# 50hz_sensor.net
KiCad netlist of a schematic drawn in EAGLE
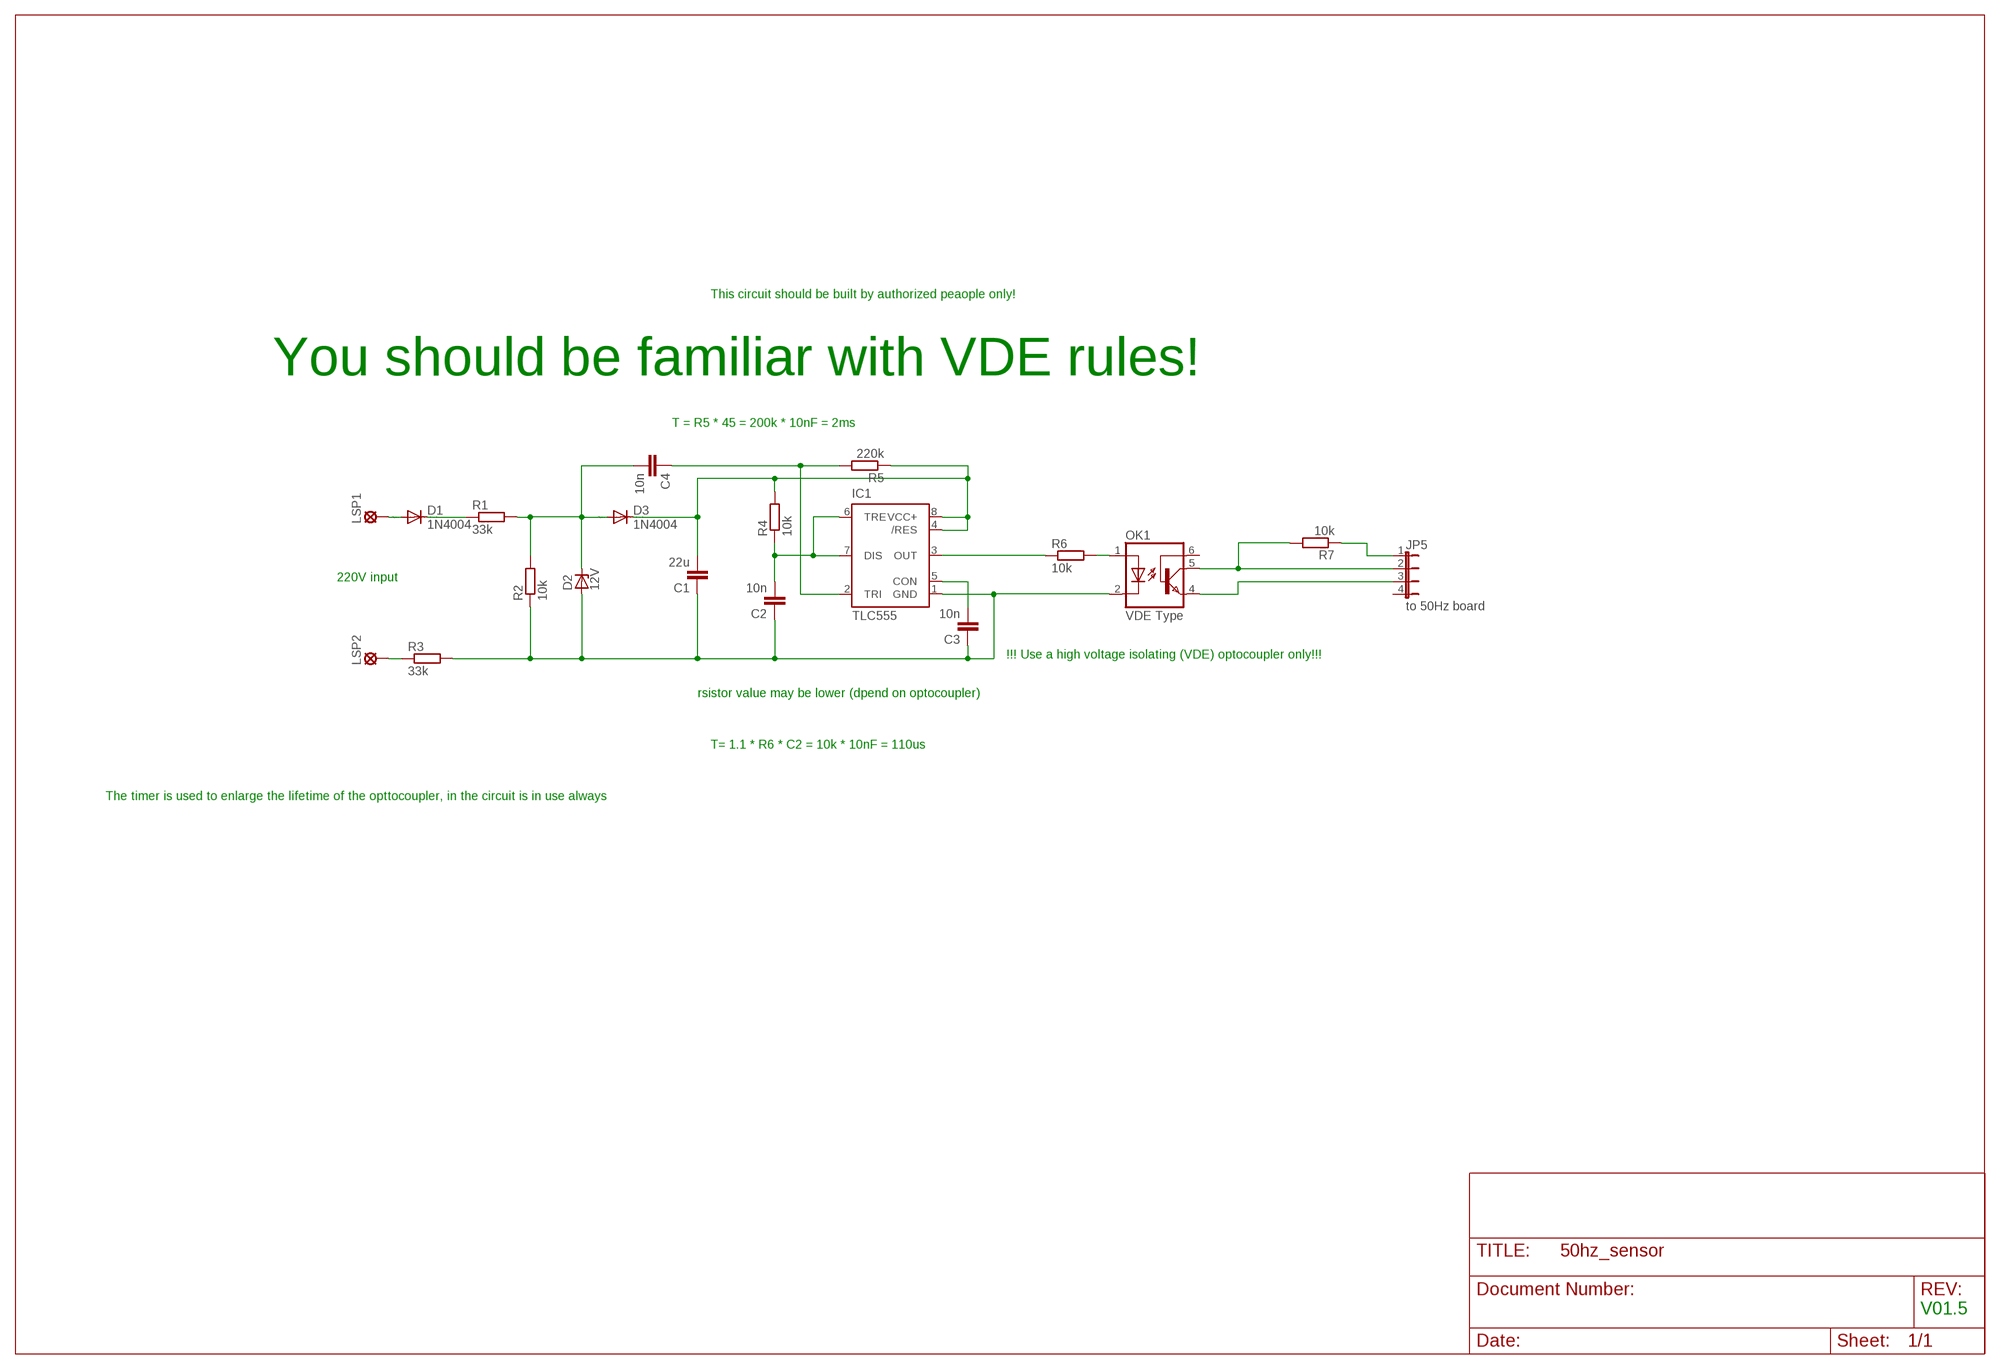
[diagram p0: schematic, sheet 1]

(export (version "E")
  (design (tool "Eeschema 10.0.6"))
  (components
    (comp (ref "C1")
      (value "22u")
      (footprint "eagle-import:C025-040X050")
      (libsource (lib "eagle-import") (part "C-EU025-040X050"))
    )
    (comp (ref "C2")
      (value "10n")
      (footprint "eagle-import:C050-025X075")
      (libsource (lib "eagle-import") (part "C-EU050-025X075"))
    )
    (comp (ref "C3")
      (value "10n")
      (footprint "eagle-import:C050-035X075")
      (libsource (lib "eagle-import") (part "C-EU050-035X075"))
    )
    (comp (ref "C4")
      (value "10n")
      (footprint "eagle-import:C050-030X075")
      (libsource (lib "eagle-import") (part "C-EU050-030X075"))
    )
    (comp (ref "D1")
      (value "1N4004")
      (footprint "eagle-import:DO41-10")
      (libsource (lib "eagle-import") (part "1N4004"))
    )
    (comp (ref "D2")
      (value "12V")
      (footprint "eagle-import:DO34Z7")
      (libsource (lib "eagle-import") (part "ZENER-DIODEDO34-7"))
    )
    (comp (ref "D3")
      (value "1N4004")
      (footprint "eagle-import:DO41-10")
      (libsource (lib "eagle-import") (part "1N4004"))
    )
    (comp (ref "IC1")
      (value "TLC555")
      (footprint "eagle-import:DIL-08")
      (fields (field (name "MF") "Arrow Electronics") (field (name "MPN") "NE555N"))
      (libsource (lib "eagle-import") (part "NE555"))
    )
    (comp (ref "JP5")
      (value "to 50Hz board")
      (footprint "eagle-import:JP4")
      (libsource (lib "eagle-import") (part "JP4E"))
    )
    (comp (ref "LSP1")
      (value "LSP11")
      (footprint "eagle-import:LSP11")
      (libsource (lib "eagle-import") (part "LSP11"))
    )
    (comp (ref "LSP2")
      (value "LSP11")
      (footprint "eagle-import:LSP11")
      (libsource (lib "eagle-import") (part "LSP11"))
    )
    (comp (ref "OK1")
      (value "VDE Type")
      (footprint "eagle-import:DIL6-04")
      (fields (field (name "MF") "FAIRCHILD SEMICONDUCTOR") (field (name "MPN") "4N28TM"))
      (libsource (lib "eagle-import") (part "4N?MT28"))
    )
    (comp (ref "R1")
      (value "33k")
      (footprint "eagle-import:0309_10")
      (libsource (lib "eagle-import") (part "R-EU_0309/10"))
    )
    (comp (ref "R2")
      (value "10k")
      (footprint "eagle-import:0309_10")
      (libsource (lib "eagle-import") (part "R-EU_0309/10"))
    )
    (comp (ref "R3")
      (value "33k")
      (footprint "eagle-import:0309_10")
      (libsource (lib "eagle-import") (part "R-EU_0309/10"))
    )
    (comp (ref "R4")
      (value "10k")
      (footprint "eagle-import:0309_10")
      (libsource (lib "eagle-import") (part "R-EU_0309/10"))
    )
    (comp (ref "R5")
      (value "220k")
      (footprint "eagle-import:0309_10")
      (libsource (lib "eagle-import") (part "R-EU_0309/10"))
    )
    (comp (ref "R6")
      (value "10k")
      (footprint "eagle-import:0309_10")
      (libsource (lib "eagle-import") (part "R-EU_0309/10"))
    )
    (comp (ref "R7")
      (value "10k")
      (footprint "eagle-import:0309_10")
      (libsource (lib "eagle-import") (part "R-EU_0309/10"))
    )
  )
  (nets
    (net (code "1") (name "Net-(C4-Pad2)") (class "Default")
      (node (ref "C4") (pin "2") (pinfunction "2_2") (pintype "passive"))
      (node (ref "D2") (pin "C") (pinfunction "C_C") (pintype "passive"))
      (node (ref "D3") (pin "A") (pinfunction "A_A") (pintype "passive"))
      (node (ref "R1") (pin "2") (pinfunction "2_2") (pintype "passive"))
      (node (ref "R2") (pin "2") (pinfunction "2_2") (pintype "passive"))
    )
    (net (code "2") (name "Net-(D1-PadA)") (class "Default")
      (node (ref "D1") (pin "A") (pinfunction "A_A") (pintype "passive"))
      (node (ref "LSP1") (pin "MP") (pinfunction "MP_MP") (pintype "passive"))
    )
    (net (code "3") (name "Net-(D1-PadC)") (class "Default")
      (node (ref "D1") (pin "C") (pinfunction "C_C") (pintype "passive"))
      (node (ref "R1") (pin "1") (pinfunction "1_1") (pintype "passive"))
    )
    (net (code "4") (name "Net-(IC1-CON)") (class "Default")
      (node (ref "C3") (pin "2") (pinfunction "2_2") (pintype "passive"))
      (node (ref "IC1") (pin "5") (pinfunction "CON_5") (pintype "input"))
    )
    (net (code "5") (name "Net-(IC1-DIS)") (class "Default")
      (node (ref "C2") (pin "2") (pinfunction "2_2") (pintype "passive"))
      (node (ref "IC1") (pin "6") (pinfunction "TRE_6") (pintype "input"))
      (node (ref "IC1") (pin "7") (pinfunction "DIS_7") (pintype "input"))
      (node (ref "R4") (pin "1") (pinfunction "1_1") (pintype "passive"))
    )
    (net (code "6") (name "Net-(IC1-GND)") (class "Default")
      (node (ref "C1") (pin "1") (pinfunction "1_1") (pintype "passive"))
      (node (ref "C2") (pin "1") (pinfunction "1_1") (pintype "passive"))
      (node (ref "C3") (pin "1") (pinfunction "1_1") (pintype "passive"))
      (node (ref "D2") (pin "A") (pinfunction "A_A") (pintype "passive"))
      (node (ref "IC1") (pin "1") (pinfunction "GND_1") (pintype "power_in"))
      (node (ref "OK1") (pin "2") (pinfunction "C_2") (pintype "passive"))
      (node (ref "R2") (pin "1") (pinfunction "1_1") (pintype "passive"))
      (node (ref "R3") (pin "2") (pinfunction "2_2") (pintype "passive"))
    )
    (net (code "7") (name "Net-(IC1-OUT)") (class "Default")
      (node (ref "IC1") (pin "3") (pinfunction "OUT_3") (pintype "output"))
      (node (ref "R6") (pin "1") (pinfunction "1_1") (pintype "passive"))
    )
    (net (code "8") (name "Net-(IC1-TRI)") (class "Default")
      (node (ref "C4") (pin "1") (pinfunction "1_1") (pintype "passive"))
      (node (ref "IC1") (pin "2") (pinfunction "TRI_2") (pintype "input"))
      (node (ref "R5") (pin "2") (pinfunction "2_2") (pintype "passive"))
    )
    (net (code "9") (name "Net-(IC1-VCC+)") (class "Default")
      (node (ref "C1") (pin "2") (pinfunction "2_2") (pintype "passive"))
      (node (ref "D3") (pin "C") (pinfunction "C_C") (pintype "passive"))
      (node (ref "IC1") (pin "4") (pinfunction "/RES_4") (pintype "input"))
      (node (ref "IC1") (pin "8") (pinfunction "VCC+_8") (pintype "power_in"))
      (node (ref "R4") (pin "2") (pinfunction "2_2") (pintype "passive"))
      (node (ref "R5") (pin "1") (pinfunction "1_1") (pintype "passive"))
    )
    (net (code "10") (name "Net-(JP5-Pad1)") (class "Default")
      (node (ref "JP5") (pin "1") (pinfunction "1_1") (pintype "passive"))
      (node (ref "R7") (pin "1") (pinfunction "1_1") (pintype "passive"))
    )
    (net (code "11") (name "Net-(LSP2-PadMP)") (class "Default")
      (node (ref "LSP2") (pin "MP") (pinfunction "MP_MP") (pintype "passive"))
      (node (ref "R3") (pin "1") (pinfunction "1_1") (pintype "passive"))
    )
    (net (code "12") (name "Net-(OK1-A)") (class "Default")
      (node (ref "OK1") (pin "1") (pinfunction "A_1") (pintype "passive"))
      (node (ref "R6") (pin "2") (pinfunction "2_2") (pintype "passive"))
    )
    (net (code "13") (name "Net-(OK1-COL)") (class "Default")
      (node (ref "JP5") (pin "2") (pinfunction "2_2") (pintype "passive"))
      (node (ref "OK1") (pin "5") (pinfunction "COL_5") (pintype "passive"))
      (node (ref "R7") (pin "2") (pinfunction "2_2") (pintype "passive"))
    )
    (net (code "14") (name "Net-(OK1-EMI)") (class "Default")
      (node (ref "JP5") (pin "3") (pinfunction "3_3") (pintype "passive"))
      (node (ref "OK1") (pin "4") (pinfunction "EMI_4") (pintype "passive"))
    )
    (net (code "15") (name "unconnected-(JP5-Pad4)") (class "Default")
      (node (ref "JP5") (pin "4") (pinfunction "4_4") (pintype "passive"))
    )
    (net (code "16") (name "unconnected-(OK1-BAS-Pad6)") (class "Default")
      (node (ref "OK1") (pin "6") (pinfunction "BAS_6") (pintype "passive"))
    )
  )
)
